# sqm-dis.net
KiCad netlist of a schematic drawn in EAGLE
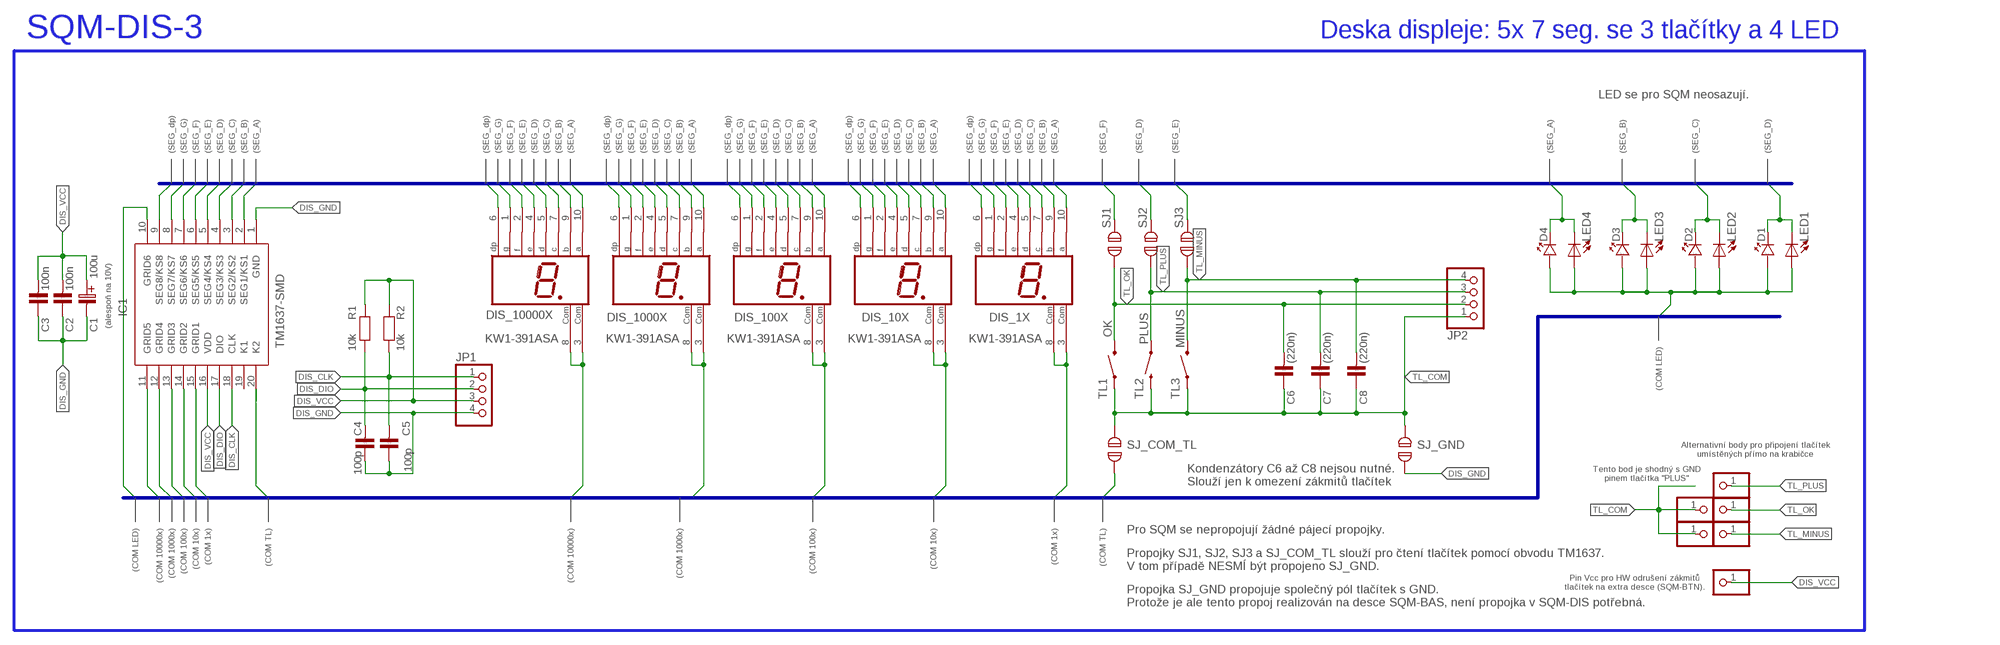
[diagram p0: schematic, sheet 1]

(export (version "E")
  (design (tool "Eeschema 10.0.6"))
  (components
    (comp (ref "C1")
      (value "100u")
      (footprint "eagle-import:C-EL_2,5")
      (libsource (lib "eagle-import") (part "C-ELEKTROLYT_2,5"))
    )
    (comp (ref "C2")
      (value "100n")
      (footprint "eagle-import:0805")
      (libsource (lib "eagle-import") (part "C-KERAMIK_SMD_0805"))
    )
    (comp (ref "C3")
      (value "100n")
      (footprint "eagle-import:0805")
      (libsource (lib "eagle-import") (part "C-KERAMIK_SMD_0805"))
    )
    (comp (ref "C4")
      (value "100p")
      (footprint "eagle-import:0805")
      (libsource (lib "eagle-import") (part "C-KERAMIK_SMD_0805"))
    )
    (comp (ref "C5")
      (value "100p")
      (footprint "eagle-import:0805")
      (libsource (lib "eagle-import") (part "C-KERAMIK_SMD_0805"))
    )
    (comp (ref "C6")
      (value "(220n)")
      (footprint "eagle-import:0805")
      (libsource (lib "eagle-import") (part "C-KERAMIK_SMD_0805"))
    )
    (comp (ref "C7")
      (value "(220n)")
      (footprint "eagle-import:0805")
      (libsource (lib "eagle-import") (part "C-KERAMIK_SMD_0805"))
    )
    (comp (ref "C8")
      (value "(220n)")
      (footprint "eagle-import:0805")
      (libsource (lib "eagle-import") (part "C-KERAMIK_SMD_0805"))
    )
    (comp (ref "D1")
      (value "LED_3")
      (footprint "eagle-import:LED_3")
      (libsource (lib "eagle-import") (part "LED_3"))
    )
    (comp (ref "D2")
      (value "LED_3")
      (footprint "eagle-import:LED_3")
      (libsource (lib "eagle-import") (part "LED_3"))
    )
    (comp (ref "D3")
      (value "LED_3")
      (footprint "eagle-import:LED_3")
      (libsource (lib "eagle-import") (part "LED_3"))
    )
    (comp (ref "D4")
      (value "LED_3")
      (footprint "eagle-import:LED_3")
      (libsource (lib "eagle-import") (part "LED_3"))
    )
    (comp (ref "DIS_1X")
      (value "KW1-391ASA")
      (footprint "eagle-import:HDSP-E")
      (libsource (lib "eagle-import") (part "SC39-11SRWA"))
    )
    (comp (ref "DIS_10X")
      (value "KW1-391ASA")
      (footprint "eagle-import:HDSP-E")
      (libsource (lib "eagle-import") (part "SC39-11SRWA"))
    )
    (comp (ref "DIS_100X")
      (value "KW1-391ASA")
      (footprint "eagle-import:HDSP-E")
      (libsource (lib "eagle-import") (part "SC39-11SRWA"))
    )
    (comp (ref "DIS_1000X")
      (value "KW1-391ASA")
      (footprint "eagle-import:HDSP-E")
      (libsource (lib "eagle-import") (part "SC39-11SRWA"))
    )
    (comp (ref "DIS_10000X")
      (value "KW1-391ASA")
      (footprint "eagle-import:HDSP-E")
      (libsource (lib "eagle-import") (part "SC39-11SRWA"))
    )
    (comp (ref "IC1")
      (value "TM1637-SMD")
      (footprint "eagle-import:SOIC127P1045X280-20N")
      (fields (field (name "MANUFACTURER_PART_NUMBER") "TM1637 (SOP)"))
      (libsource (lib "eagle-import") (part "TM1637__SOP_"))
    )
    (comp (ref "JP1")
      (value "PINHD-1X4")
      (footprint "eagle-import:1X04")
      (libsource (lib "eagle-import") (part "PINHD-1X4"))
    )
    (comp (ref "JP2")
      (value "PINHD-1X4")
      (footprint "eagle-import:1X04")
      (libsource (lib "eagle-import") (part "PINHD-1X4"))
    )
    (comp (ref "JP3")
      (value "PINHD-1X1")
      (footprint "eagle-import:1X01")
      (libsource (lib "eagle-import") (part "PINHD-1X1"))
    )
    (comp (ref "JP4")
      (value "PINHD-1X1")
      (footprint "eagle-import:1X01")
      (libsource (lib "eagle-import") (part "PINHD-1X1"))
    )
    (comp (ref "JP5")
      (value "PINHD-1X1")
      (footprint "eagle-import:1X01")
      (libsource (lib "eagle-import") (part "PINHD-1X1"))
    )
    (comp (ref "JP6")
      (value "PINHD-1X1")
      (footprint "eagle-import:1X01")
      (libsource (lib "eagle-import") (part "PINHD-1X1"))
    )
    (comp (ref "JP7")
      (value "PINHD-1X1")
      (footprint "eagle-import:1X01")
      (libsource (lib "eagle-import") (part "PINHD-1X1"))
    )
    (comp (ref "JP8")
      (value "PINHD-1X1")
      (footprint "eagle-import:1X01")
      (libsource (lib "eagle-import") (part "PINHD-1X1"))
    )
    (comp (ref "LED1")
      (value "LEDCHIP-LED0805")
      (footprint "eagle-import:CHIP-LED0805")
      (libsource (lib "eagle-import") (part "LEDCHIP-LED0805"))
    )
    (comp (ref "LED2")
      (value "LEDCHIP-LED0805")
      (footprint "eagle-import:CHIP-LED0805")
      (libsource (lib "eagle-import") (part "LEDCHIP-LED0805"))
    )
    (comp (ref "LED3")
      (value "LEDCHIP-LED0805")
      (footprint "eagle-import:CHIP-LED0805")
      (libsource (lib "eagle-import") (part "LEDCHIP-LED0805"))
    )
    (comp (ref "LED4")
      (value "LEDCHIP-LED0805")
      (footprint "eagle-import:CHIP-LED0805")
      (libsource (lib "eagle-import") (part "LEDCHIP-LED0805"))
    )
    (comp (ref "R1")
      (value "10k")
      (footprint "eagle-import:0805")
      (libsource (lib "eagle-import") (part "R_SMD_0805"))
    )
    (comp (ref "R2")
      (value "10k")
      (footprint "eagle-import:0805")
      (libsource (lib "eagle-import") (part "R_SMD_0805"))
    )
    (comp (ref "SJ1")
      (value "SJ")
      (footprint "eagle-import:SJ_2S-NO")
      (libsource (lib "eagle-import") (part "SOLDERJUMPER"))
    )
    (comp (ref "SJ2")
      (value "SJ")
      (footprint "eagle-import:SJ_2S-NO")
      (libsource (lib "eagle-import") (part "SOLDERJUMPER"))
    )
    (comp (ref "SJ3")
      (value "SJ")
      (footprint "eagle-import:SJ_2S-NO")
      (libsource (lib "eagle-import") (part "SOLDERJUMPER"))
    )
    (comp (ref "SJ_COM_TL")
      (value "SJ")
      (footprint "eagle-import:SJ_2S-NO")
      (libsource (lib "eagle-import") (part "SOLDERJUMPER"))
    )
    (comp (ref "SJ_GND")
      (value "SJ")
      (footprint "eagle-import:SJ_2S-NO")
      (libsource (lib "eagle-import") (part "SOLDERJUMPER"))
    )
    (comp (ref "TL1")
      (value "OK")
      (footprint "eagle-import:TACTILE_SWITCH_PTH_6.0MM")
      (libsource (lib "eagle-import") (part "MOMENTARY-SWITCH-SPST-PTH-6.0MM"))
    )
    (comp (ref "TL2")
      (value "PLUS")
      (footprint "eagle-import:TACTILE_SWITCH_PTH_6.0MM")
      (libsource (lib "eagle-import") (part "MOMENTARY-SWITCH-SPST-PTH-6.0MM"))
    )
    (comp (ref "TL3")
      (value "MINUS")
      (footprint "eagle-import:TACTILE_SWITCH_PTH_6.0MM")
      (libsource (lib "eagle-import") (part "MOMENTARY-SWITCH-SPST-PTH-6.0MM"))
    )
  )
  (nets
    (net (code "1") (name "/COM_BUS0") (class "Default")
      (node (ref "DIS_1X") (pin "3") (pinfunction "COM_3") (pintype "passive"))
      (node (ref "DIS_1X") (pin "8") (pinfunction "COM_8") (pintype "passive"))
      (node (ref "IC1") (pin "15") (pinfunction "GRID1_15") (pintype "bidirectional"))
    )
    (net (code "2") (name "/COM_BUS1") (class "Default")
      (node (ref "DIS_10X") (pin "3") (pinfunction "COM_3") (pintype "passive"))
      (node (ref "DIS_10X") (pin "8") (pinfunction "COM_8") (pintype "passive"))
      (node (ref "IC1") (pin "14") (pinfunction "GRID2_14") (pintype "bidirectional"))
    )
    (net (code "3") (name "/COM_BUS2") (class "Default")
      (node (ref "DIS_100X") (pin "3") (pinfunction "COM_3") (pintype "passive"))
      (node (ref "DIS_100X") (pin "8") (pinfunction "COM_8") (pintype "passive"))
      (node (ref "IC1") (pin "13") (pinfunction "GRID3_13") (pintype "bidirectional"))
    )
    (net (code "4") (name "/COM_BUS3") (class "Default")
      (node (ref "DIS_1000X") (pin "3") (pinfunction "COM_3") (pintype "passive"))
      (node (ref "DIS_1000X") (pin "8") (pinfunction "COM_8") (pintype "passive"))
      (node (ref "IC1") (pin "12") (pinfunction "GRID4_12") (pintype "bidirectional"))
    )
    (net (code "5") (name "/COM_BUS4") (class "Default")
      (node (ref "DIS_10000X") (pin "3") (pinfunction "COM_3") (pintype "passive"))
      (node (ref "DIS_10000X") (pin "8") (pinfunction "COM_8") (pintype "passive"))
      (node (ref "IC1") (pin "11") (pinfunction "GRID5_11") (pintype "bidirectional"))
    )
    (net (code "6") (name "/COM_BUS5") (class "Default")
      (node (ref "IC1") (pin "20") (pinfunction "K2_20") (pintype "bidirectional"))
      (node (ref "SJ_COM_TL") (pin "1") (pinfunction "P$1_1") (pintype "bidirectional"))
    )
    (net (code "7") (name "/COM_BUS6") (class "Default")
      (node (ref "D1") (pin "A") (pinfunction "A_A") (pintype "passive"))
      (node (ref "D2") (pin "A") (pinfunction "A_A") (pintype "passive"))
      (node (ref "D3") (pin "A") (pinfunction "A_A") (pintype "passive"))
      (node (ref "D4") (pin "A") (pinfunction "A_A") (pintype "passive"))
      (node (ref "IC1") (pin "10") (pinfunction "GRID6_10") (pintype "bidirectional"))
      (node (ref "LED1") (pin "A") (pinfunction "A_A") (pintype "passive"))
      (node (ref "LED2") (pin "A") (pinfunction "A_A") (pintype "passive"))
      (node (ref "LED3") (pin "A") (pinfunction "A_A") (pintype "passive"))
      (node (ref "LED4") (pin "A") (pinfunction "A_A") (pintype "passive"))
    )
    (net (code "8") (name "/SEG_BUS0") (class "Default")
      (node (ref "D4") (pin "K") (pinfunction "K_K") (pintype "passive"))
      (node (ref "DIS_10000X") (pin "10") (pinfunction "A_10") (pintype "passive"))
      (node (ref "DIS_1000X") (pin "10") (pinfunction "A_10") (pintype "passive"))
      (node (ref "DIS_100X") (pin "10") (pinfunction "A_10") (pintype "passive"))
      (node (ref "DIS_10X") (pin "10") (pinfunction "A_10") (pintype "passive"))
      (node (ref "DIS_1X") (pin "10") (pinfunction "A_10") (pintype "passive"))
      (node (ref "IC1") (pin "2") (pinfunction "SEG1/KS1_2") (pintype "bidirectional"))
      (node (ref "LED4") (pin "C") (pinfunction "C_C") (pintype "passive"))
    )
    (net (code "9") (name "/SEG_BUS1") (class "Default")
      (node (ref "D3") (pin "K") (pinfunction "K_K") (pintype "passive"))
      (node (ref "DIS_10000X") (pin "9") (pinfunction "B_9") (pintype "passive"))
      (node (ref "DIS_1000X") (pin "9") (pinfunction "B_9") (pintype "passive"))
      (node (ref "DIS_100X") (pin "9") (pinfunction "B_9") (pintype "passive"))
      (node (ref "DIS_10X") (pin "9") (pinfunction "B_9") (pintype "passive"))
      (node (ref "DIS_1X") (pin "9") (pinfunction "B_9") (pintype "passive"))
      (node (ref "IC1") (pin "3") (pinfunction "SEG2/KS2_3") (pintype "bidirectional"))
      (node (ref "LED3") (pin "C") (pinfunction "C_C") (pintype "passive"))
    )
    (net (code "10") (name "/SEG_BUS2") (class "Default")
      (node (ref "D2") (pin "K") (pinfunction "K_K") (pintype "passive"))
      (node (ref "DIS_10000X") (pin "7") (pinfunction "C_7") (pintype "passive"))
      (node (ref "DIS_1000X") (pin "7") (pinfunction "C_7") (pintype "passive"))
      (node (ref "DIS_100X") (pin "7") (pinfunction "C_7") (pintype "passive"))
      (node (ref "DIS_10X") (pin "7") (pinfunction "C_7") (pintype "passive"))
      (node (ref "DIS_1X") (pin "7") (pinfunction "C_7") (pintype "passive"))
      (node (ref "IC1") (pin "4") (pinfunction "SEG3/KS3_4") (pintype "bidirectional"))
      (node (ref "LED2") (pin "C") (pinfunction "C_C") (pintype "passive"))
    )
    (net (code "11") (name "/SEG_BUS3") (class "Default")
      (node (ref "D1") (pin "K") (pinfunction "K_K") (pintype "passive"))
      (node (ref "DIS_10000X") (pin "5") (pinfunction "D_5") (pintype "passive"))
      (node (ref "DIS_1000X") (pin "5") (pinfunction "D_5") (pintype "passive"))
      (node (ref "DIS_100X") (pin "5") (pinfunction "D_5") (pintype "passive"))
      (node (ref "DIS_10X") (pin "5") (pinfunction "D_5") (pintype "passive"))
      (node (ref "DIS_1X") (pin "5") (pinfunction "D_5") (pintype "passive"))
      (node (ref "IC1") (pin "5") (pinfunction "SEG4/KS4_5") (pintype "bidirectional"))
      (node (ref "LED1") (pin "C") (pinfunction "C_C") (pintype "passive"))
      (node (ref "SJ2") (pin "2") (pinfunction "P$2_2") (pintype "bidirectional"))
    )
    (net (code "12") (name "/SEG_BUS4") (class "Default")
      (node (ref "DIS_10000X") (pin "4") (pinfunction "E_4") (pintype "passive"))
      (node (ref "DIS_1000X") (pin "4") (pinfunction "E_4") (pintype "passive"))
      (node (ref "DIS_100X") (pin "4") (pinfunction "E_4") (pintype "passive"))
      (node (ref "DIS_10X") (pin "4") (pinfunction "E_4") (pintype "passive"))
      (node (ref "DIS_1X") (pin "4") (pinfunction "E_4") (pintype "passive"))
      (node (ref "IC1") (pin "6") (pinfunction "SEG5/KS5_6") (pintype "bidirectional"))
      (node (ref "SJ3") (pin "2") (pinfunction "P$2_2") (pintype "bidirectional"))
    )
    (net (code "13") (name "/SEG_BUS5") (class "Default")
      (node (ref "DIS_10000X") (pin "2") (pinfunction "F_2") (pintype "passive"))
      (node (ref "DIS_1000X") (pin "2") (pinfunction "F_2") (pintype "passive"))
      (node (ref "DIS_100X") (pin "2") (pinfunction "F_2") (pintype "passive"))
      (node (ref "DIS_10X") (pin "2") (pinfunction "F_2") (pintype "passive"))
      (node (ref "DIS_1X") (pin "2") (pinfunction "F_2") (pintype "passive"))
      (node (ref "IC1") (pin "7") (pinfunction "SEG6/KS6_7") (pintype "bidirectional"))
      (node (ref "SJ1") (pin "2") (pinfunction "P$2_2") (pintype "bidirectional"))
    )
    (net (code "14") (name "/SEG_BUS6") (class "Default")
      (node (ref "DIS_10000X") (pin "1") (pinfunction "G_1") (pintype "passive"))
      (node (ref "DIS_1000X") (pin "1") (pinfunction "G_1") (pintype "passive"))
      (node (ref "DIS_100X") (pin "1") (pinfunction "G_1") (pintype "passive"))
      (node (ref "DIS_10X") (pin "1") (pinfunction "G_1") (pintype "passive"))
      (node (ref "DIS_1X") (pin "1") (pinfunction "G_1") (pintype "passive"))
      (node (ref "IC1") (pin "8") (pinfunction "SEG7/KS7_8") (pintype "bidirectional"))
    )
    (net (code "15") (name "/SEG_BUS7") (class "Default")
      (node (ref "DIS_10000X") (pin "6") (pinfunction "DP_6") (pintype "passive"))
      (node (ref "DIS_1000X") (pin "6") (pinfunction "DP_6") (pintype "passive"))
      (node (ref "DIS_100X") (pin "6") (pinfunction "DP_6") (pintype "passive"))
      (node (ref "DIS_10X") (pin "6") (pinfunction "DP_6") (pintype "passive"))
      (node (ref "DIS_1X") (pin "6") (pinfunction "DP_6") (pintype "passive"))
      (node (ref "IC1") (pin "9") (pinfunction "SEG8/KS8_9") (pintype "bidirectional"))
    )
    (net (code "16") (name "DIS_CLK") (class "Default")
      (node (ref "C5") (pin "2") (pinfunction "2_2") (pintype "passive"))
      (node (ref "IC1") (pin "18") (pinfunction "CLK_18") (pintype "bidirectional"))
      (node (ref "JP1") (pin "1") (pinfunction "1_1") (pintype "passive"))
      (node (ref "R2") (pin "1") (pinfunction "1_1") (pintype "passive"))
    )
    (net (code "17") (name "DIS_DIO") (class "Default")
      (node (ref "C4") (pin "2") (pinfunction "2_2") (pintype "passive"))
      (node (ref "IC1") (pin "17") (pinfunction "DIO_17") (pintype "bidirectional"))
      (node (ref "JP1") (pin "2") (pinfunction "2_2") (pintype "passive"))
      (node (ref "R1") (pin "1") (pinfunction "1_1") (pintype "passive"))
    )
    (net (code "18") (name "DIS_GND") (class "Default")
      (node (ref "C1") (pin "C-") (pinfunction "C_EL-_C-") (pintype "passive"))
      (node (ref "C2") (pin "1") (pinfunction "1_1") (pintype "passive"))
      (node (ref "C3") (pin "1") (pinfunction "1_1") (pintype "passive"))
      (node (ref "C4") (pin "1") (pinfunction "1_1") (pintype "passive"))
      (node (ref "C5") (pin "1") (pinfunction "1_1") (pintype "passive"))
      (node (ref "IC1") (pin "1") (pinfunction "GND_1") (pintype "bidirectional"))
      (node (ref "JP1") (pin "4") (pinfunction "4_4") (pintype "passive"))
      (node (ref "SJ_GND") (pin "1") (pinfunction "P$1_1") (pintype "bidirectional"))
    )
    (net (code "19") (name "DIS_VCC") (class "Default")
      (node (ref "C1") (pin "C+") (pinfunction "C_EL+_C+") (pintype "passive"))
      (node (ref "C2") (pin "2") (pinfunction "2_2") (pintype "passive"))
      (node (ref "C3") (pin "2") (pinfunction "2_2") (pintype "passive"))
      (node (ref "IC1") (pin "16") (pinfunction "VDD_16") (pintype "bidirectional"))
      (node (ref "JP1") (pin "3") (pinfunction "3_3") (pintype "passive"))
      (node (ref "JP3") (pin "1") (pinfunction "1_1") (pintype "passive"))
      (node (ref "R1") (pin "2") (pinfunction "2_2") (pintype "passive"))
      (node (ref "R2") (pin "2") (pinfunction "2_2") (pintype "passive"))
    )
    (net (code "20") (name "TL_COM") (class "Default")
      (node (ref "C6") (pin "1") (pinfunction "1_1") (pintype "passive"))
      (node (ref "C7") (pin "1") (pinfunction "1_1") (pintype "passive"))
      (node (ref "C8") (pin "1") (pinfunction "1_1") (pintype "passive"))
      (node (ref "JP2") (pin "1") (pinfunction "1_1") (pintype "passive"))
      (node (ref "JP7") (pin "1") (pinfunction "1_1") (pintype "passive"))
      (node (ref "JP8") (pin "1") (pinfunction "1_1") (pintype "passive"))
      (node (ref "SJ_COM_TL") (pin "2") (pinfunction "P$2_2") (pintype "bidirectional"))
      (node (ref "SJ_GND") (pin "2") (pinfunction "P$2_2") (pintype "bidirectional"))
      (node (ref "TL1") (pin "1") (pinfunction "1_1") (pintype "passive"))
      (node (ref "TL2") (pin "3") (pinfunction "2_3") (pintype "passive"))
      (node (ref "TL3") (pin "1") (pinfunction "1_1") (pintype "passive"))
    )
    (net (code "21") (name "TL_MINUS") (class "Default")
      (node (ref "C8") (pin "2") (pinfunction "2_2") (pintype "passive"))
      (node (ref "JP2") (pin "4") (pinfunction "4_4") (pintype "passive"))
      (node (ref "JP6") (pin "1") (pinfunction "1_1") (pintype "passive"))
      (node (ref "SJ3") (pin "1") (pinfunction "P$1_1") (pintype "bidirectional"))
      (node (ref "TL3") (pin "3") (pinfunction "2_3") (pintype "passive"))
    )
    (net (code "22") (name "TL_OK") (class "Default")
      (node (ref "C6") (pin "2") (pinfunction "2_2") (pintype "passive"))
      (node (ref "JP2") (pin "2") (pinfunction "2_2") (pintype "passive"))
      (node (ref "JP4") (pin "1") (pinfunction "1_1") (pintype "passive"))
      (node (ref "SJ1") (pin "1") (pinfunction "P$1_1") (pintype "bidirectional"))
      (node (ref "TL1") (pin "3") (pinfunction "2_3") (pintype "passive"))
    )
    (net (code "23") (name "TL_PLUS") (class "Default")
      (node (ref "C7") (pin "2") (pinfunction "2_2") (pintype "passive"))
      (node (ref "JP2") (pin "3") (pinfunction "3_3") (pintype "passive"))
      (node (ref "JP5") (pin "1") (pinfunction "1_1") (pintype "passive"))
      (node (ref "SJ2") (pin "1") (pinfunction "P$1_1") (pintype "bidirectional"))
      (node (ref "TL2") (pin "1") (pinfunction "1_1") (pintype "passive"))
    )
    (net (code "24") (name "unconnected-(IC1-K1-Pad19)") (class "Default")
      (node (ref "IC1") (pin "19") (pinfunction "K1_19") (pintype "bidirectional"))
    )
  )
)
